# MCU.net
KiCad netlist of a schematic drawn in Altium Designer
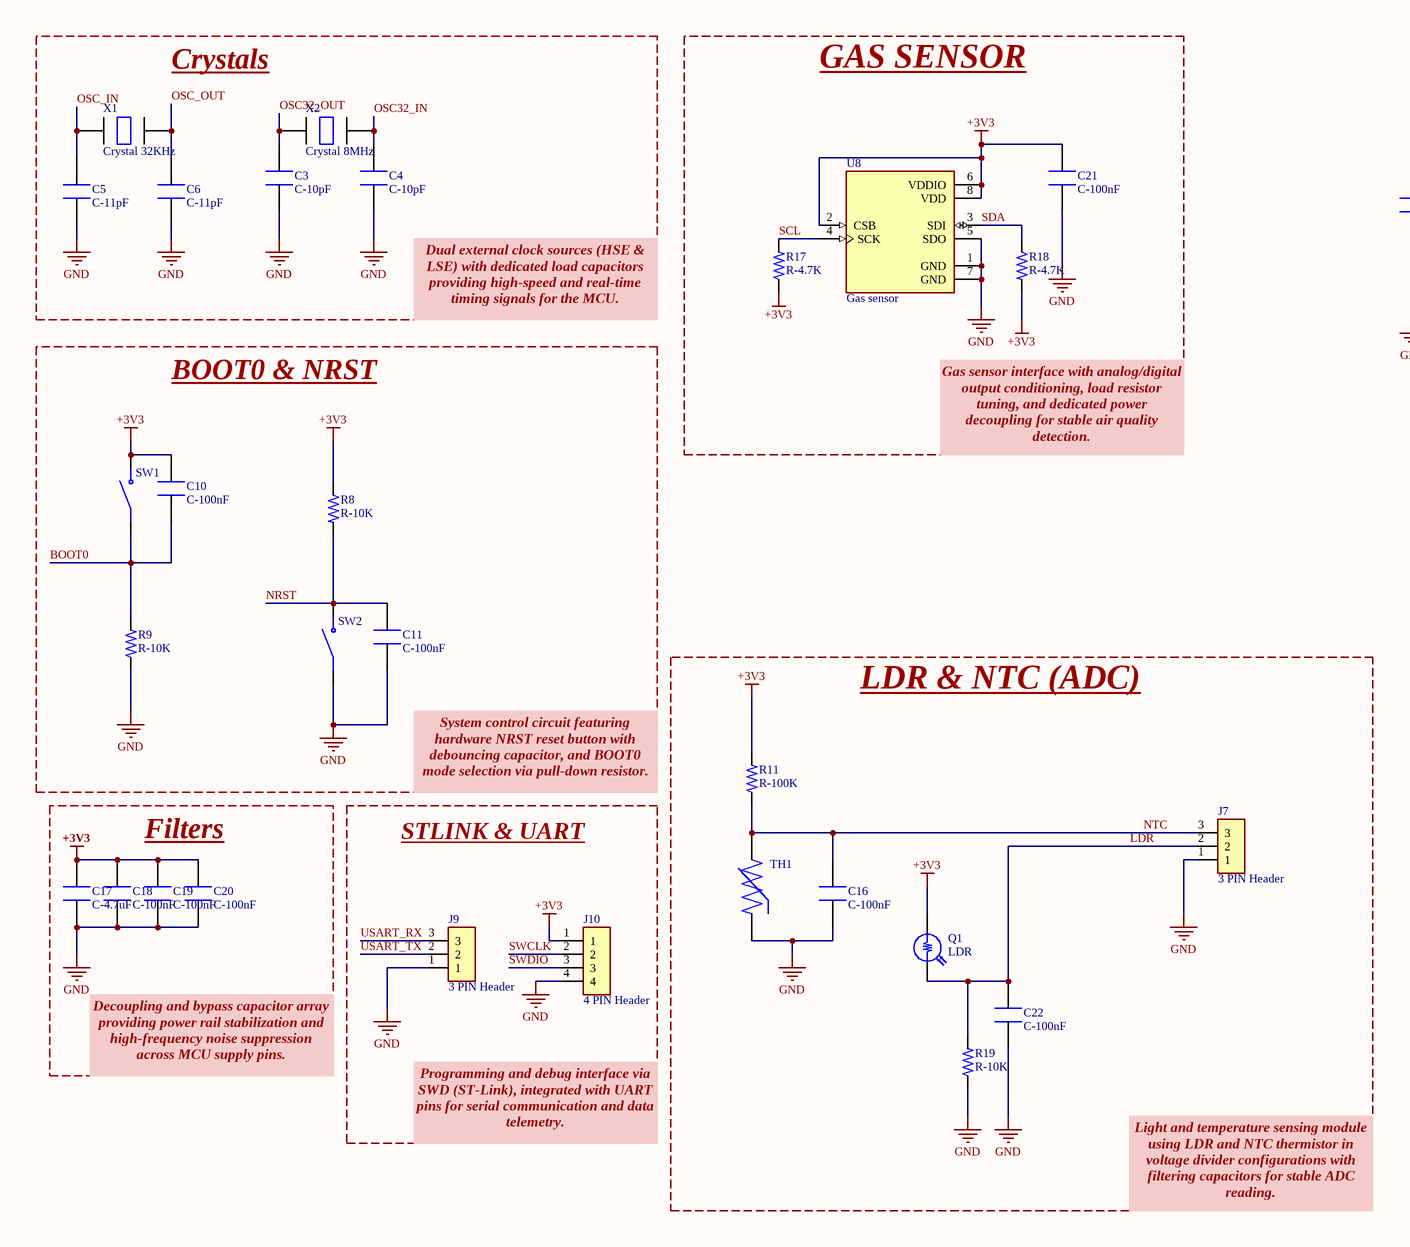
[diagram p0: MCU.SchDoc, left]
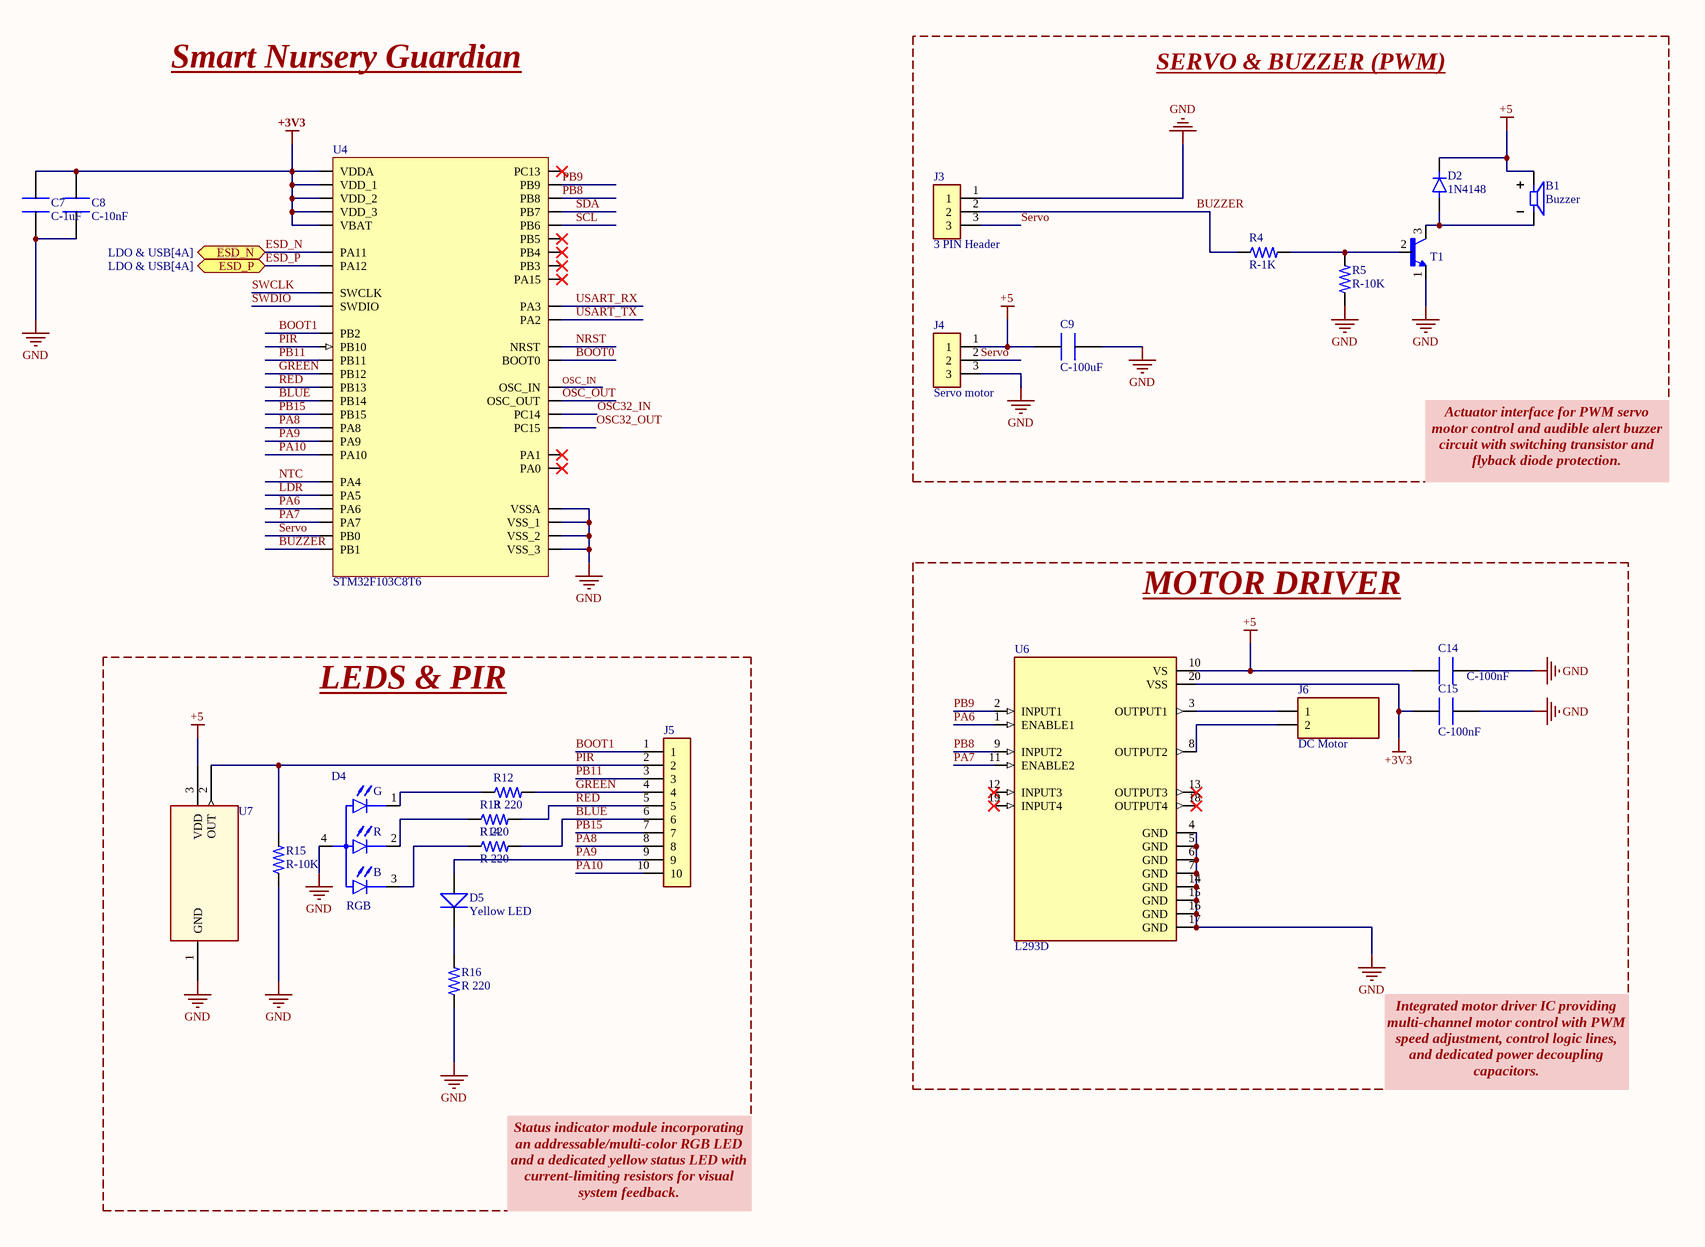
[diagram p1: MCU.SchDoc, right]

(export (version "E")
  (design (tool "Eeschema 10.0.6"))
  (components
    (comp (ref "B1")
      (value "Buzzer")
      (footprint "Buzzer")
      (description "Through Hole Alarms, Buzzers, and Sirens RoHS")
      (fields (field (name "MFR") "CUI") (field (name "MFR PART#") "CMI-1210-5-95T"))
      (libsource (lib "Schlib1") (part "Buzzer"))
    )
    (comp (ref "C3")
      (value "C-10pF")
      (footprint "C-10pF")
      (fields (field (name "MFR") "Samsung Electro-Mechanics") (field (name "MFR PART #") "CL10C100JB8NNNC"))
      (libsource (lib "Schlib1") (part "C-10pF"))
    )
    (comp (ref "C4")
      (value "C-10pF")
      (footprint "C-10pF")
      (fields (field (name "MFR") "Samsung Electro-Mechanics") (field (name "MFR PART #") "CL10C100JB8NNNC"))
      (libsource (lib "Schlib1") (part "C-10pF"))
    )
    (comp (ref "C5")
      (value "C-11pF")
      (footprint "C-10pF")
      (fields (field (name "MFR") "muRata") (field (name "MFR PART") "GRM0335C1E110JA01D"))
      (libsource (lib "Schlib1") (part "C-11pF"))
    )
    (comp (ref "C6")
      (value "C-11pF")
      (footprint "C-10pF")
      (fields (field (name "MFR") "muRata") (field (name "MFR PART") "GRM0335C1E110JA01D"))
      (libsource (lib "Schlib1") (part "C-11pF"))
    )
    (comp (ref "C7")
      (value "C-1uF")
      (footprint "CAPC0804X80N")
      (fields (field (name "MFR") "Samsung Electro-Mechanics") (field (name "MFR PART#") "CL10B105KA8NNNC"))
      (libsource (lib "Schlib1") (part "C-1uF"))
    )
    (comp (ref "C8")
      (value "C-10nF")
      (footprint "CAPC0804X80N")
      (fields (field (name "MFR") "YAGEO") (field (name "MFR PART #") "CC0603KRX7R9BB103"))
      (libsource (lib "Schlib1") (part "C-10nF"))
    )
    (comp (ref "C9")
      (value "C-100uF")
      (footprint "CAPC1709X35N")
      (description "CAP CER 100uF 6.3V X5R 1206")
      (fields (field (name "MFR") "Samsung Electro-Mechanics") (field (name "MFR PART#") "CL31A107MQHNNNE"))
      (libsource (lib "Schlib1") (part "C-100uF"))
    )
    (comp (ref "C10")
      (value "C-100nF")
      (footprint "CAPC1007X45N")
      (fields (field (name "MFR") "TDK") (field (name "MFR PART#") "CGA5L2X7R2A104KT0Y0U"))
      (libsource (lib "Schlib1") (part "C-100nF"))
    )
    (comp (ref "C11")
      (value "C-100nF")
      (footprint "CAPC1007X45N")
      (fields (field (name "MFR") "TDK") (field (name "MFR PART#") "CGA5L2X7R2A104KT0Y0U"))
      (libsource (lib "Schlib1") (part "C-100nF"))
    )
    (comp (ref "C14")
      (value "C-100nF")
      (footprint "CAPC1007X45N")
      (fields (field (name "MFR") "TDK") (field (name "MFR PART#") "CGA5L2X7R2A104KT0Y0U"))
      (libsource (lib "Schlib1") (part "C-100nF"))
    )
    (comp (ref "C15")
      (value "C-100nF")
      (footprint "CAPC1007X45N")
      (fields (field (name "MFR") "TDK") (field (name "MFR PART#") "CGA5L2X7R2A104KT0Y0U"))
      (libsource (lib "Schlib1") (part "C-100nF"))
    )
    (comp (ref "C16")
      (value "C-100nF")
      (footprint "CAPC1007X45N")
      (fields (field (name "MFR") "TDK") (field (name "MFR PART#") "CGA5L2X7R2A104KT0Y0U"))
      (libsource (lib "Schlib1") (part "C-100nF"))
    )
    (comp (ref "C17")
      (value "C-4.7uF")
      (footprint "CAPC1007X45N")
      (fields (field (name "MFR") "SAMYOUNG") (field (name "MFR PART #") "MVK 50V4.7 5*5.2"))
      (libsource (lib "Schlib1") (part "C-4.7uF"))
    )
    (comp (ref "C18")
      (value "C-100nF")
      (footprint "CAPC1007X45N")
      (fields (field (name "MFR") "TDK") (field (name "MFR PART#") "CGA5L2X7R2A104KT0Y0U"))
      (libsource (lib "Schlib1") (part "C-100nF"))
    )
    (comp (ref "C19")
      (value "C-100nF")
      (footprint "CAPC1007X45N")
      (fields (field (name "MFR") "TDK") (field (name "MFR PART#") "CGA5L2X7R2A104KT0Y0U"))
      (libsource (lib "Schlib1") (part "C-100nF"))
    )
    (comp (ref "C20")
      (value "C-100nF")
      (footprint "CAPC1007X45N")
      (fields (field (name "MFR") "TDK") (field (name "MFR PART#") "CGA5L2X7R2A104KT0Y0U"))
      (libsource (lib "Schlib1") (part "C-100nF"))
    )
    (comp (ref "C21")
      (value "C-100nF")
      (footprint "CAPC1007X45N")
      (fields (field (name "MFR") "TDK") (field (name "MFR PART#") "CGA5L2X7R2A104KT0Y0U"))
      (libsource (lib "Schlib1") (part "C-100nF"))
    )
    (comp (ref "C22")
      (value "C-100nF")
      (footprint "CAPC1007X45N")
      (fields (field (name "MFR") "TDK") (field (name "MFR PART#") "CGA5L2X7R2A104KT0Y0U"))
      (libsource (lib "Schlib1") (part "C-100nF"))
    )
    (comp (ref "D2")
      (value "1N4148")
      (footprint "DIOM3413X180N")
      (description "DIODE GP 100V 200mA DO-35")
      (fields (field (name "MFR") "onsemi"))
      (libsource (lib "Schlib1") (part "1N4148"))
    )
    (comp (ref "D4")
      (value "RGB")
      (footprint "RGB")
      (description "12x12 Red, Green, Blue(RGB) LED Dot Matrix and Cluster RoHS")
      (fields (field (name "MFR") "Inolux") (field (name "MFR PART#") "INCM88001"))
      (libsource (lib "Schlib1") (part "RGB"))
    )
    (comp (ref "D5")
      (value "Yellow LED")
      (footprint "Green LED")
      (description "LED YELLOW WATER CLEAR 0402 SMD")
      (fields (field (name "MFR") "YONGYUTAI") (field (name "MFR PART#") "YLED0402Y"))
      (libsource (lib "Schlib1") (part "Yellow LED"))
    )
    (comp (ref "J3")
      (value "3 PIN Header")
      (footprint "PIN 3 Header")
      (libsource (lib "Schlib1") (part "3 PIN Header"))
    )
    (comp (ref "J4")
      (value "Servo motor")
      (footprint "PIN 3 Header")
      (libsource (lib "Schlib1") (part "3 PIN Header"))
    )
    (comp (ref "J5")
      (value "10 PIN Header")
      (footprint "10 PIN Header")
      (libsource (lib "Schlib1") (part "10 PIN Header"))
    )
    (comp (ref "J6")
      (value "DC Motor")
      (footprint "2 PIN Header")
      (description "Pin Header 2 Position Dual Row Through Hole -55℃~+125℃")
      (fields (field (name "MFR") "Samtec") (field (name "MFR PART#") "MTSW-101-09-L-D-515"))
      (libsource (lib "Schlib1") (part "2 PIN Header"))
    )
    (comp (ref "J7")
      (value "3 PIN Header")
      (footprint "PIN 3 Header")
      (libsource (lib "") (part "3 PIN Header_1"))
    )
    (comp (ref "J9")
      (value "3 PIN Header")
      (footprint "PIN 3 Header")
      (libsource (lib "") (part "3 PIN Header_2"))
    )
    (comp (ref "J10")
      (value "4 PIN Header")
      (footprint "Header 4pin")
      (fields
        (field (name "MFR") "hanxia")
        (field (name "MFR PART #") "HX PH254-01-04-Z-L11.5 straight pin header")
      )
      (libsource (lib "Schlib1") (part "4 PIN Header"))
    )
    (comp (ref "Q1")
      (value "LDR")
      (footprint "LDR")
      (description "Silicon NPN Phototransistor, RoHS Compliant")
      (fields (field (name "MFR") "VISHAY") (field (name "MFR PART#") "TEMT1020"))
      (libsource (lib "Schlib1") (part "LDR"))
    )
    (comp (ref "R4")
      (value "R-1K")
      (footprint "RESC0804X45N")
      (fields
        (field (name "MFR") "FOJAN")
        (field (name "MFR PART #") "FRC0603F1001TS")
        (field (name "SPN PART#") "C2907002")
      )
      (libsource (lib "Schlib1") (part "R-1K"))
    )
    (comp (ref "R5")
      (value "R-10K")
      (footprint "R-10K")
      (fields
        (field (name "MFR") "YAGEO")
        (field (name "MFR PART#") "RC0603FR-0710KL")
        (field (name "SPN PART #") "C98220")
      )
      (libsource (lib "Schlib1") (part "R-10K"))
    )
    (comp (ref "R8")
      (value "R-10K")
      (footprint "R-10K")
      (fields
        (field (name "MFR") "YAGEO")
        (field (name "MFR PART#") "RC0603FR-0710KL")
        (field (name "SPN PART #") "C98220")
      )
      (libsource (lib "Schlib1") (part "R-10K"))
    )
    (comp (ref "R9")
      (value "R-10K")
      (footprint "R-10K")
      (fields
        (field (name "MFR") "YAGEO")
        (field (name "MFR PART#") "RC0603FR-0710KL")
        (field (name "SPN PART #") "C98220")
      )
      (libsource (lib "Schlib1") (part "R-10K"))
    )
    (comp (ref "R11")
      (value "R-100K")
      (footprint "RESC0503X35N")
      (description "RES 100kΩ ±1% 62.5mW 0402")
      (fields (field (name "MFR") "YAGEO") (field (name "MFR PART#") "RC0402FR-07100KL"))
      (libsource (lib "Schlib1") (part "R-100K"))
    )
    (comp (ref "R12")
      (value "R 220")
      (footprint "R-220")
      (fields (field (name "MFR") "UNI-ROYAL") (field (name "MFR PART #") "0603WAF2200T5E"))
      (libsource (lib "Schlib1") (part "R 220"))
    )
    (comp (ref "R13")
      (value "R 220")
      (footprint "R-220")
      (fields (field (name "MFR") "UNI-ROYAL") (field (name "MFR PART #") "0603WAF2200T5E"))
      (libsource (lib "Schlib1") (part "R 220"))
    )
    (comp (ref "R14")
      (value "R 220")
      (footprint "R-220")
      (fields (field (name "MFR") "UNI-ROYAL") (field (name "MFR PART #") "0603WAF2200T5E"))
      (libsource (lib "Schlib1") (part "R 220"))
    )
    (comp (ref "R15")
      (value "R-10K")
      (footprint "R-10K")
      (fields
        (field (name "MFR") "YAGEO")
        (field (name "MFR PART#") "RC0603FR-0710KL")
        (field (name "SPN PART #") "C98220")
      )
      (libsource (lib "Schlib1") (part "R-10K"))
    )
    (comp (ref "R16")
      (value "R 220")
      (footprint "R-220")
      (fields (field (name "MFR") "UNI-ROYAL") (field (name "MFR PART #") "0603WAF2200T5E"))
      (libsource (lib "Schlib1") (part "R 220"))
    )
    (comp (ref "R17")
      (value "R-4.7K")
      (footprint "RESC1007X50N")
      (description "RES 4.7kΩ ±1% 100mW 0603")
      (fields (field (name "MFR") "YAGEO") (field (name "MFR PART#") "RC0603FR-074K7L"))
      (libsource (lib "Schlib1") (part "R-4.7K"))
    )
    (comp (ref "R18")
      (value "R-4.7K")
      (footprint "RESC1007X50N")
      (description "RES 4.7kΩ ±1% 100mW 0603")
      (fields (field (name "MFR") "YAGEO") (field (name "MFR PART#") "RC0603FR-074K7L"))
      (libsource (lib "Schlib1") (part "R-4.7K"))
    )
    (comp (ref "R19")
      (value "R-10K")
      (footprint "R-10K")
      (fields
        (field (name "MFR") "YAGEO")
        (field (name "MFR PART#") "RC0603FR-0710KL")
        (field (name "SPN PART #") "C98220")
      )
      (libsource (lib "Schlib1") (part "R-10K"))
    )
    (comp (ref "SW1")
      (value "SWITCH")
      (footprint "SWITCH")
      (fields
        (field (name "MFR") "C&K")
        (field (name "MFR PART#") "L101011ML04Q")
        (field (name "SPN PART #") "C2799508")
      )
      (libsource (lib "Schlib1") (part "SWITCH"))
    )
    (comp (ref "SW2")
      (value "SWITCH")
      (footprint "SWITCH")
      (fields
        (field (name "MFR") "C&K")
        (field (name "MFR PART#") "L101011ML04Q")
        (field (name "SPN PART #") "C2799508")
      )
      (libsource (lib "Schlib1") (part "SWITCH"))
    )
    (comp (ref "T1")
      (value "2N2222")
      (footprint "2N2222")
      (description "NPN Plastic-Encapsulate Transistors")
      (fields (field (name "MFR") "HXY MOSFET") (field (name "MFR PART#") "2N2222A"))
      (libsource (lib "Schlib1") (part "2N2222"))
    )
    (comp (ref "TH1")
      (value "NTC Thermistor")
      (footprint "NTC")
      (description "THERMISTOR NTC 100kΩ 4250K 0402")
      (fields (field (name "MFR") "muRata") (field (name "MFR PART#") "NCU15WF104D60RC"))
      (libsource (lib "Schlib1") (part "NTC Thermistor"))
    )
    (comp (ref "U4")
      (value "STM32F103C8T6")
      (footprint "STM32")
      (fields (field (name "MFR") "ST"))
      (libsource (lib "Schlib1") (part "STM32F103C8T6"))
    )
    (comp (ref "U6")
      (value "L293D")
      (footprint "L293D")
      (description "PUSH-PULL FOUR CHANNEL DRIVER WITH DIODES")
      (fields (field (name "MFR") "ST") (field (name "MFR PART#") "L293DD"))
      (libsource (lib "Schlib1") (part "L293D"))
    )
    (comp (ref "U7")
      (value "PIR")
      (footprint "PIR")
      (description "PIRs motion sensor")
      (fields (field (name "MFR") "PANASONIC") (field (name "MFR PART#") "EKMC1601111"))
      (libsource (lib "Schlib1") (part "PIR"))
    )
    (comp (ref "U8")
      (value "Gas sensor")
      (footprint "Gas sensor")
      (fields (field (name "MFR") "Bosch") (field (name "MFR PART#") "BME688"))
      (libsource (lib "Schlib1") (part "Gas sensor"))
    )
    (comp (ref "X1")
      (value "Crystal 32KHz")
      (footprint "Crystal 32KHz")
      (description "Crystal 32kHz ±100ppm 11pF 35kΩ DT-26")
      (fields (field (name "MFR") "EPSON") (field (name "MFR PART#") "C-2 32.0000K-P:PBFREE"))
      (libsource (lib "Schlib1") (part "Crystal 32KHz"))
    )
    (comp (ref "X2")
      (value "Crystal 8MHz")
      (footprint "crystal 8Mz")
      (description "CRYSTAL 8MHz 12pF SMD")
      (fields (field (name "MFR") "YXC Crystal Oscillators") (field (name "MFR PART #") "X32258MOB4SI"))
      (libsource (lib "Schlib1") (part "Crystal 8MHz"))
    )
  )
  (nets
    (net (code "1") (name "+3V3") (class "Default")
      (node (ref "C10") (pin "2") (pinfunction "2_2") (pintype "passive"))
      (node (ref "C15") (pin "1") (pinfunction "1_1") (pintype "passive"))
      (node (ref "C17") (pin "2") (pinfunction "2_2") (pintype "passive"))
      (node (ref "C18") (pin "2") (pinfunction "2_2") (pintype "passive"))
      (node (ref "C19") (pin "2") (pinfunction "2_2") (pintype "passive"))
      (node (ref "C20") (pin "2") (pinfunction "2_2") (pintype "passive"))
      (node (ref "C21") (pin "2") (pinfunction "2_2") (pintype "passive"))
      (node (ref "C7") (pin "2") (pinfunction "2_2") (pintype "passive"))
      (node (ref "C8") (pin "2") (pinfunction "2_2") (pintype "passive"))
      (node (ref "J10") (pin "1") (pinfunction "1_1") (pintype "passive"))
      (node (ref "Q1") (pin "1") (pinfunction "1_1") (pintype "passive"))
      (node (ref "R11") (pin "2") (pinfunction "2_2") (pintype "passive"))
      (node (ref "R17") (pin "1") (pinfunction "1_1") (pintype "passive"))
      (node (ref "R18") (pin "2") (pinfunction "2_2") (pintype "passive"))
      (node (ref "R8") (pin "1") (pinfunction "1_1") (pintype "passive"))
      (node (ref "SW1") (pin "2") (pinfunction "2_2") (pintype "passive"))
      (node (ref "U4") (pin "1") (pinfunction "VBAT_1") (pintype "passive"))
      (node (ref "U4") (pin "24") (pinfunction "VDD_1_24") (pintype "passive"))
      (node (ref "U4") (pin "36") (pinfunction "VDD_2_36") (pintype "passive"))
      (node (ref "U4") (pin "48") (pinfunction "VDD_3_48") (pintype "passive"))
      (node (ref "U4") (pin "9") (pinfunction "VDDA_9") (pintype "passive"))
      (node (ref "U6") (pin "20") (pinfunction "VSS_20") (pintype "power_in"))
      (node (ref "U8") (pin "2") (pinfunction "CSB_2") (pintype "input"))
      (node (ref "U8") (pin "6") (pinfunction "VDDIO_6") (pintype "power_in"))
      (node (ref "U8") (pin "8") (pinfunction "VDD_8") (pintype "power_in"))
    )
    (net (code "2") (name "+5") (class "Default")
      (node (ref "B1") (pin "P") (pinfunction "P_P") (pintype "passive"))
      (node (ref "C14") (pin "2") (pinfunction "2_2") (pintype "passive"))
      (node (ref "C9") (pin "1") (pinfunction "1_1") (pintype "passive"))
      (node (ref "D2") (pin "K") (pinfunction "K_K") (pintype "passive"))
      (node (ref "J4") (pin "1") (pinfunction "1_1") (pintype "passive"))
      (node (ref "U6") (pin "10") (pinfunction "VS_10") (pintype "power_in"))
      (node (ref "U7") (pin "3") (pinfunction "VDD_3") (pintype "power_in"))
    )
    (net (code "3") (name "/BLUE") (class "Default")
      (node (ref "J5") (pin "6") (pinfunction "6_6") (pintype "passive"))
      (node (ref "R14") (pin "2") (pinfunction "2_2") (pintype "passive"))
      (node (ref "U4") (pin "27") (pinfunction "PB14_27") (pintype "bidirectional"))
    )
    (net (code "4") (name "/BOOT0") (class "Default")
      (node (ref "C10") (pin "1") (pinfunction "1_1") (pintype "passive"))
      (node (ref "R9") (pin "2") (pinfunction "2_2") (pintype "passive"))
      (node (ref "SW1") (pin "1") (pinfunction "1_1") (pintype "passive"))
      (node (ref "U4") (pin "44") (pinfunction "BOOT0_44") (pintype "passive"))
    )
    (net (code "5") (name "/BOOT1") (class "Default")
      (node (ref "J5") (pin "1") (pinfunction "1_1") (pintype "passive"))
      (node (ref "U4") (pin "20") (pinfunction "PB2_20") (pintype "bidirectional"))
    )
    (net (code "6") (name "/BUZZER") (class "Default")
      (node (ref "J3") (pin "2") (pinfunction "2_2") (pintype "passive"))
      (node (ref "R4") (pin "1") (pinfunction "1_1") (pintype "passive"))
      (node (ref "U4") (pin "19") (pinfunction "PB1_19") (pintype "bidirectional"))
    )
    (net (code "7") (name "/ESD_N") (class "Default")
      (node (ref "U4") (pin "32") (pinfunction "PA11_32") (pintype "passive"))
    )
    (net (code "8") (name "/ESD_P") (class "Default")
      (node (ref "U4") (pin "33") (pinfunction "PA12_33") (pintype "passive"))
    )
    (net (code "9") (name "/GREEN") (class "Default")
      (node (ref "J5") (pin "4") (pinfunction "4_4") (pintype "passive"))
      (node (ref "R12") (pin "2") (pinfunction "2_2") (pintype "passive"))
      (node (ref "U4") (pin "25") (pinfunction "PB12_25") (pintype "bidirectional"))
    )
    (net (code "10") (name "/LDR") (class "Default")
      (node (ref "C22") (pin "2") (pinfunction "2_2") (pintype "passive"))
      (node (ref "J7") (pin "2") (pinfunction "2_2") (pintype "passive"))
      (node (ref "Q1") (pin "2") (pinfunction "2_2") (pintype "passive"))
      (node (ref "R19") (pin "2") (pinfunction "2_2") (pintype "passive"))
      (node (ref "U4") (pin "15") (pinfunction "PA5_15") (pintype "bidirectional"))
    )
    (net (code "11") (name "/NRST") (class "Default")
      (node (ref "C11") (pin "2") (pinfunction "2_2") (pintype "passive"))
      (node (ref "R8") (pin "2") (pinfunction "2_2") (pintype "passive"))
      (node (ref "SW2") (pin "2") (pinfunction "2_2") (pintype "passive"))
      (node (ref "U4") (pin "7") (pinfunction "NRST_7") (pintype "passive"))
    )
    (net (code "12") (name "/NTC") (class "Default")
      (node (ref "C16") (pin "2") (pinfunction "2_2") (pintype "passive"))
      (node (ref "J7") (pin "3") (pinfunction "3_3") (pintype "passive"))
      (node (ref "R11") (pin "1") (pinfunction "1_1") (pintype "passive"))
      (node (ref "TH1") (pin "2") (pinfunction "2_2") (pintype "passive"))
      (node (ref "U4") (pin "14") (pinfunction "PA4_14") (pintype "bidirectional"))
    )
    (net (code "13") (name "/OSC32_IN") (class "Default")
      (node (ref "C4") (pin "2") (pinfunction "2_2") (pintype "passive"))
      (node (ref "U4") (pin "3") (pinfunction "PC14_3") (pintype "passive"))
      (node (ref "X2") (pin "2") (pinfunction "2_2") (pintype "passive"))
    )
    (net (code "14") (name "/OSC32_OUT") (class "Default")
      (node (ref "C3") (pin "2") (pinfunction "2_2") (pintype "passive"))
      (node (ref "U4") (pin "4") (pinfunction "PC15_4") (pintype "passive"))
      (node (ref "X2") (pin "1") (pinfunction "1_1") (pintype "passive"))
    )
    (net (code "15") (name "/OSC_IN") (class "Default")
      (node (ref "C5") (pin "2") (pinfunction "2_2") (pintype "passive"))
      (node (ref "U4") (pin "5") (pinfunction "OSC_IN_5") (pintype "passive"))
      (node (ref "X1") (pin "1") (pinfunction "1_1") (pintype "passive"))
    )
    (net (code "16") (name "/OSC_OUT") (class "Default")
      (node (ref "C6") (pin "2") (pinfunction "2_2") (pintype "passive"))
      (node (ref "U4") (pin "6") (pinfunction "OSC_OUT_6") (pintype "passive"))
      (node (ref "X1") (pin "2") (pinfunction "2_2") (pintype "passive"))
    )
    (net (code "17") (name "/PA6") (class "Default")
      (node (ref "U4") (pin "16") (pinfunction "PA6_16") (pintype "bidirectional"))
      (node (ref "U6") (pin "1") (pinfunction "ENABLE1_1") (pintype "input"))
    )
    (net (code "18") (name "/PA7") (class "Default")
      (node (ref "U4") (pin "17") (pinfunction "PA7_17") (pintype "bidirectional"))
      (node (ref "U6") (pin "11") (pinfunction "ENABLE2_11") (pintype "input"))
    )
    (net (code "19") (name "/PA8") (class "Default")
      (node (ref "J5") (pin "8") (pinfunction "8_8") (pintype "passive"))
      (node (ref "U4") (pin "29") (pinfunction "PA8_29") (pintype "bidirectional"))
    )
    (net (code "20") (name "/PA9") (class "Default")
      (node (ref "D5") (pin "2") (pinfunction "2_2") (pintype "passive"))
      (node (ref "J5") (pin "9") (pinfunction "9_9") (pintype "passive"))
      (node (ref "U4") (pin "30") (pinfunction "PA9_30") (pintype "bidirectional"))
    )
    (net (code "21") (name "/PA10") (class "Default")
      (node (ref "J5") (pin "10") (pinfunction "10_10") (pintype "passive"))
      (node (ref "U4") (pin "31") (pinfunction "PA10_31") (pintype "bidirectional"))
    )
    (net (code "22") (name "/PB8") (class "Default")
      (node (ref "U4") (pin "45") (pinfunction "PB8_45") (pintype "bidirectional"))
      (node (ref "U6") (pin "9") (pinfunction "INPUT2_9") (pintype "input"))
    )
    (net (code "23") (name "/PB9") (class "Default")
      (node (ref "U4") (pin "46") (pinfunction "PB9_46") (pintype "bidirectional"))
      (node (ref "U6") (pin "2") (pinfunction "INPUT1_2") (pintype "input"))
    )
    (net (code "24") (name "/PB11") (class "Default")
      (node (ref "J5") (pin "3") (pinfunction "3_3") (pintype "passive"))
      (node (ref "U4") (pin "22") (pinfunction "PB11_22") (pintype "bidirectional"))
    )
    (net (code "25") (name "/PB15") (class "Default")
      (node (ref "J5") (pin "7") (pinfunction "7_7") (pintype "passive"))
      (node (ref "U4") (pin "28") (pinfunction "PB15_28") (pintype "bidirectional"))
    )
    (net (code "26") (name "/PIR") (class "Default")
      (node (ref "J5") (pin "2") (pinfunction "2_2") (pintype "passive"))
      (node (ref "R15") (pin "2") (pinfunction "2_2") (pintype "passive"))
      (node (ref "U4") (pin "21") (pinfunction "PB10_21") (pintype "input"))
      (node (ref "U7") (pin "2") (pinfunction "OUT_2") (pintype "output"))
    )
    (net (code "27") (name "/RED") (class "Default")
      (node (ref "J5") (pin "5") (pinfunction "5_5") (pintype "passive"))
      (node (ref "R13") (pin "2") (pinfunction "2_2") (pintype "passive"))
      (node (ref "U4") (pin "26") (pinfunction "PB13_26") (pintype "bidirectional"))
    )
    (net (code "28") (name "/SCL") (class "Default")
      (node (ref "R17") (pin "2") (pinfunction "2_2") (pintype "passive"))
      (node (ref "U4") (pin "42") (pinfunction "PB6_42") (pintype "bidirectional"))
      (node (ref "U8") (pin "4") (pinfunction "SCK_4") (pintype "input"))
    )
    (net (code "29") (name "/SDA") (class "Default")
      (node (ref "R18") (pin "1") (pinfunction "1_1") (pintype "passive"))
      (node (ref "U4") (pin "43") (pinfunction "PB7_43") (pintype "bidirectional"))
      (node (ref "U8") (pin "3") (pinfunction "SDI_3") (pintype "bidirectional"))
    )
    (net (code "30") (name "/SWCLK") (class "Default")
      (node (ref "J10") (pin "2") (pinfunction "2_2") (pintype "passive"))
      (node (ref "U4") (pin "37") (pinfunction "SWCLK_37") (pintype "passive"))
    )
    (net (code "31") (name "/SWDIO") (class "Default")
      (node (ref "J10") (pin "3") (pinfunction "3_3") (pintype "passive"))
      (node (ref "U4") (pin "34") (pinfunction "SWDIO_34") (pintype "passive"))
    )
    (net (code "32") (name "/Servo") (class "Default")
      (node (ref "J3") (pin "3") (pinfunction "3_3") (pintype "passive"))
      (node (ref "J4") (pin "2") (pinfunction "2_2") (pintype "passive"))
      (node (ref "U4") (pin "18") (pinfunction "PB0_18") (pintype "bidirectional"))
    )
    (net (code "33") (name "/USART_RX") (class "Default")
      (node (ref "J9") (pin "3") (pinfunction "3_3") (pintype "passive"))
      (node (ref "U4") (pin "13") (pinfunction "PA3_13") (pintype "bidirectional"))
    )
    (net (code "34") (name "/USART_TX") (class "Default")
      (node (ref "J9") (pin "2") (pinfunction "2_2") (pintype "passive"))
      (node (ref "U4") (pin "12") (pinfunction "PA2_12") (pintype "bidirectional"))
    )
    (net (code "35") (name "GND") (class "Default")
      (node (ref "C11") (pin "1") (pinfunction "1_1") (pintype "passive"))
      (node (ref "C14") (pin "1") (pinfunction "1_1") (pintype "passive"))
      (node (ref "C15") (pin "2") (pinfunction "2_2") (pintype "passive"))
      (node (ref "C16") (pin "1") (pinfunction "1_1") (pintype "passive"))
      (node (ref "C17") (pin "1") (pinfunction "1_1") (pintype "passive"))
      (node (ref "C18") (pin "1") (pinfunction "1_1") (pintype "passive"))
      (node (ref "C19") (pin "1") (pinfunction "1_1") (pintype "passive"))
      (node (ref "C20") (pin "1") (pinfunction "1_1") (pintype "passive"))
      (node (ref "C21") (pin "1") (pinfunction "1_1") (pintype "passive"))
      (node (ref "C22") (pin "1") (pinfunction "1_1") (pintype "passive"))
      (node (ref "C3") (pin "1") (pinfunction "1_1") (pintype "passive"))
      (node (ref "C4") (pin "1") (pinfunction "1_1") (pintype "passive"))
      (node (ref "C5") (pin "1") (pinfunction "1_1") (pintype "passive"))
      (node (ref "C6") (pin "1") (pinfunction "1_1") (pintype "passive"))
      (node (ref "C7") (pin "1") (pinfunction "1_1") (pintype "passive"))
      (node (ref "C8") (pin "1") (pinfunction "1_1") (pintype "passive"))
      (node (ref "C9") (pin "2") (pinfunction "2_2") (pintype "passive"))
      (node (ref "D4") (pin "4") (pinfunction "A_4") (pintype "passive"))
      (node (ref "J10") (pin "4") (pinfunction "4_4") (pintype "passive"))
      (node (ref "J3") (pin "1") (pinfunction "1_1") (pintype "passive"))
      (node (ref "J4") (pin "3") (pinfunction "3_3") (pintype "passive"))
      (node (ref "J7") (pin "1") (pinfunction "1_1") (pintype "passive"))
      (node (ref "J9") (pin "1") (pinfunction "1_1") (pintype "passive"))
      (node (ref "R15") (pin "1") (pinfunction "1_1") (pintype "passive"))
      (node (ref "R16") (pin "1") (pinfunction "1_1") (pintype "passive"))
      (node (ref "R19") (pin "1") (pinfunction "1_1") (pintype "passive"))
      (node (ref "R5") (pin "1") (pinfunction "1_1") (pintype "passive"))
      (node (ref "R9") (pin "1") (pinfunction "1_1") (pintype "passive"))
      (node (ref "SW2") (pin "1") (pinfunction "1_1") (pintype "passive"))
      (node (ref "T1") (pin "1") (pinfunction "E_1") (pintype "passive"))
      (node (ref "TH1") (pin "1") (pinfunction "1_1") (pintype "passive"))
      (node (ref "U4") (pin "23") (pinfunction "VSS_1_23") (pintype "passive"))
      (node (ref "U4") (pin "35") (pinfunction "VSS_2_35") (pintype "passive"))
      (node (ref "U4") (pin "47") (pinfunction "VSS_3_47") (pintype "passive"))
      (node (ref "U4") (pin "8") (pinfunction "VSSA_8") (pintype "passive"))
      (node (ref "U6") (pin "14") (pinfunction "GND_14") (pintype "power_in"))
      (node (ref "U6") (pin "15") (pinfunction "GND_15") (pintype "power_in"))
      (node (ref "U6") (pin "16") (pinfunction "GND_16") (pintype "power_in"))
      (node (ref "U6") (pin "17") (pinfunction "GND_17") (pintype "power_in"))
      (node (ref "U6") (pin "4") (pinfunction "GND_4") (pintype "power_in"))
      (node (ref "U6") (pin "5") (pinfunction "GND_5") (pintype "power_in"))
      (node (ref "U6") (pin "6") (pinfunction "GND_6") (pintype "power_in"))
      (node (ref "U6") (pin "7") (pinfunction "GND_7") (pintype "power_in"))
      (node (ref "U7") (pin "1") (pinfunction "GND_1") (pintype "power_in"))
      (node (ref "U8") (pin "1") (pinfunction "GND_1") (pintype "power_in"))
      (node (ref "U8") (pin "5") (pinfunction "SDO_5") (pintype "passive"))
      (node (ref "U8") (pin "7") (pinfunction "GND_7") (pintype "power_in"))
    )
    (net (code "36") (name "Net-(D4-C1)") (class "Default")
      (node (ref "D4") (pin "1") (pinfunction "C1_1") (pintype "passive"))
      (node (ref "R12") (pin "1") (pinfunction "1_1") (pintype "passive"))
    )
    (net (code "37") (name "Net-(D4-C2)") (class "Default")
      (node (ref "D4") (pin "2") (pinfunction "C2_2") (pintype "passive"))
      (node (ref "R13") (pin "1") (pinfunction "1_1") (pintype "passive"))
    )
    (net (code "38") (name "Net-(D4-C3)") (class "Default")
      (node (ref "D4") (pin "3") (pinfunction "C3_3") (pintype "passive"))
      (node (ref "R14") (pin "1") (pinfunction "1_1") (pintype "passive"))
    )
    (net (code "39") (name "Net-(D5-Pad1)") (class "Default")
      (node (ref "D5") (pin "1") (pinfunction "1_1") (pintype "passive"))
      (node (ref "R16") (pin "2") (pinfunction "2_2") (pintype "passive"))
    )
    (net (code "40") (name "Net-(T1-B)") (class "Default")
      (node (ref "R4") (pin "2") (pinfunction "2_2") (pintype "passive"))
      (node (ref "R5") (pin "2") (pinfunction "2_2") (pintype "passive"))
      (node (ref "T1") (pin "2") (pinfunction "B_2") (pintype "passive"))
    )
    (net (code "41") (name "Net-(T1-C)") (class "Default")
      (node (ref "B1") (pin "N") (pinfunction "N_N") (pintype "passive"))
      (node (ref "D2") (pin "A") (pinfunction "A_A") (pintype "passive"))
      (node (ref "T1") (pin "3") (pinfunction "C_3") (pintype "passive"))
    )
    (net (code "42") (name "Net-(U6-OUTPUT1)") (class "Default")
      (node (ref "J6") (pin "1") (pinfunction "1_1") (pintype "passive"))
      (node (ref "U6") (pin "3") (pinfunction "OUTPUT1_3") (pintype "output"))
    )
    (net (code "43") (name "Net-(U6-OUTPUT2)") (class "Default")
      (node (ref "J6") (pin "2") (pinfunction "2_2") (pintype "passive"))
      (node (ref "U6") (pin "8") (pinfunction "OUTPUT2_8") (pintype "output"))
    )
    (net (code "44") (name "unconnected-(U4-PA0-Pad10)") (class "Default")
      (node (ref "U4") (pin "10") (pinfunction "PA0_10") (pintype "bidirectional+no_connect"))
    )
    (net (code "45") (name "unconnected-(U4-PA1-Pad11)") (class "Default")
      (node (ref "U4") (pin "11") (pinfunction "PA1_11") (pintype "bidirectional+no_connect"))
    )
    (net (code "46") (name "unconnected-(U4-PA15-Pad38)") (class "Default")
      (node (ref "U4") (pin "38") (pinfunction "PA15_38") (pintype "bidirectional+no_connect"))
    )
    (net (code "47") (name "unconnected-(U4-PB3-Pad39)") (class "Default")
      (node (ref "U4") (pin "39") (pinfunction "PB3_39") (pintype "bidirectional+no_connect"))
    )
    (net (code "48") (name "unconnected-(U4-PB4-Pad40)") (class "Default")
      (node (ref "U4") (pin "40") (pinfunction "PB4_40") (pintype "bidirectional+no_connect"))
    )
    (net (code "49") (name "unconnected-(U4-PB5-Pad41)") (class "Default")
      (node (ref "U4") (pin "41") (pinfunction "PB5_41") (pintype "bidirectional+no_connect"))
    )
    (net (code "50") (name "unconnected-(U4-PC13-Pad2)") (class "Default")
      (node (ref "U4") (pin "2") (pinfunction "PC13_2") (pintype "bidirectional+no_connect"))
    )
    (net (code "51") (name "unconnected-(U6-INPUT3-Pad12)") (class "Default")
      (node (ref "U6") (pin "12") (pinfunction "INPUT3_12") (pintype "input+no_connect"))
    )
    (net (code "52") (name "unconnected-(U6-INPUT4-Pad19)") (class "Default")
      (node (ref "U6") (pin "19") (pinfunction "INPUT4_19") (pintype "input+no_connect"))
    )
    (net (code "53") (name "unconnected-(U6-OUTPUT3-Pad13)") (class "Default")
      (node (ref "U6") (pin "13") (pinfunction "OUTPUT3_13") (pintype "output+no_connect"))
    )
    (net (code "54") (name "unconnected-(U6-OUTPUT4-Pad18)") (class "Default")
      (node (ref "U6") (pin "18") (pinfunction "OUTPUT4_18") (pintype "output+no_connect"))
    )
  )
)
